# RGB_Matrix.net
KiCad netlist of a schematic drawn in Altium Designer
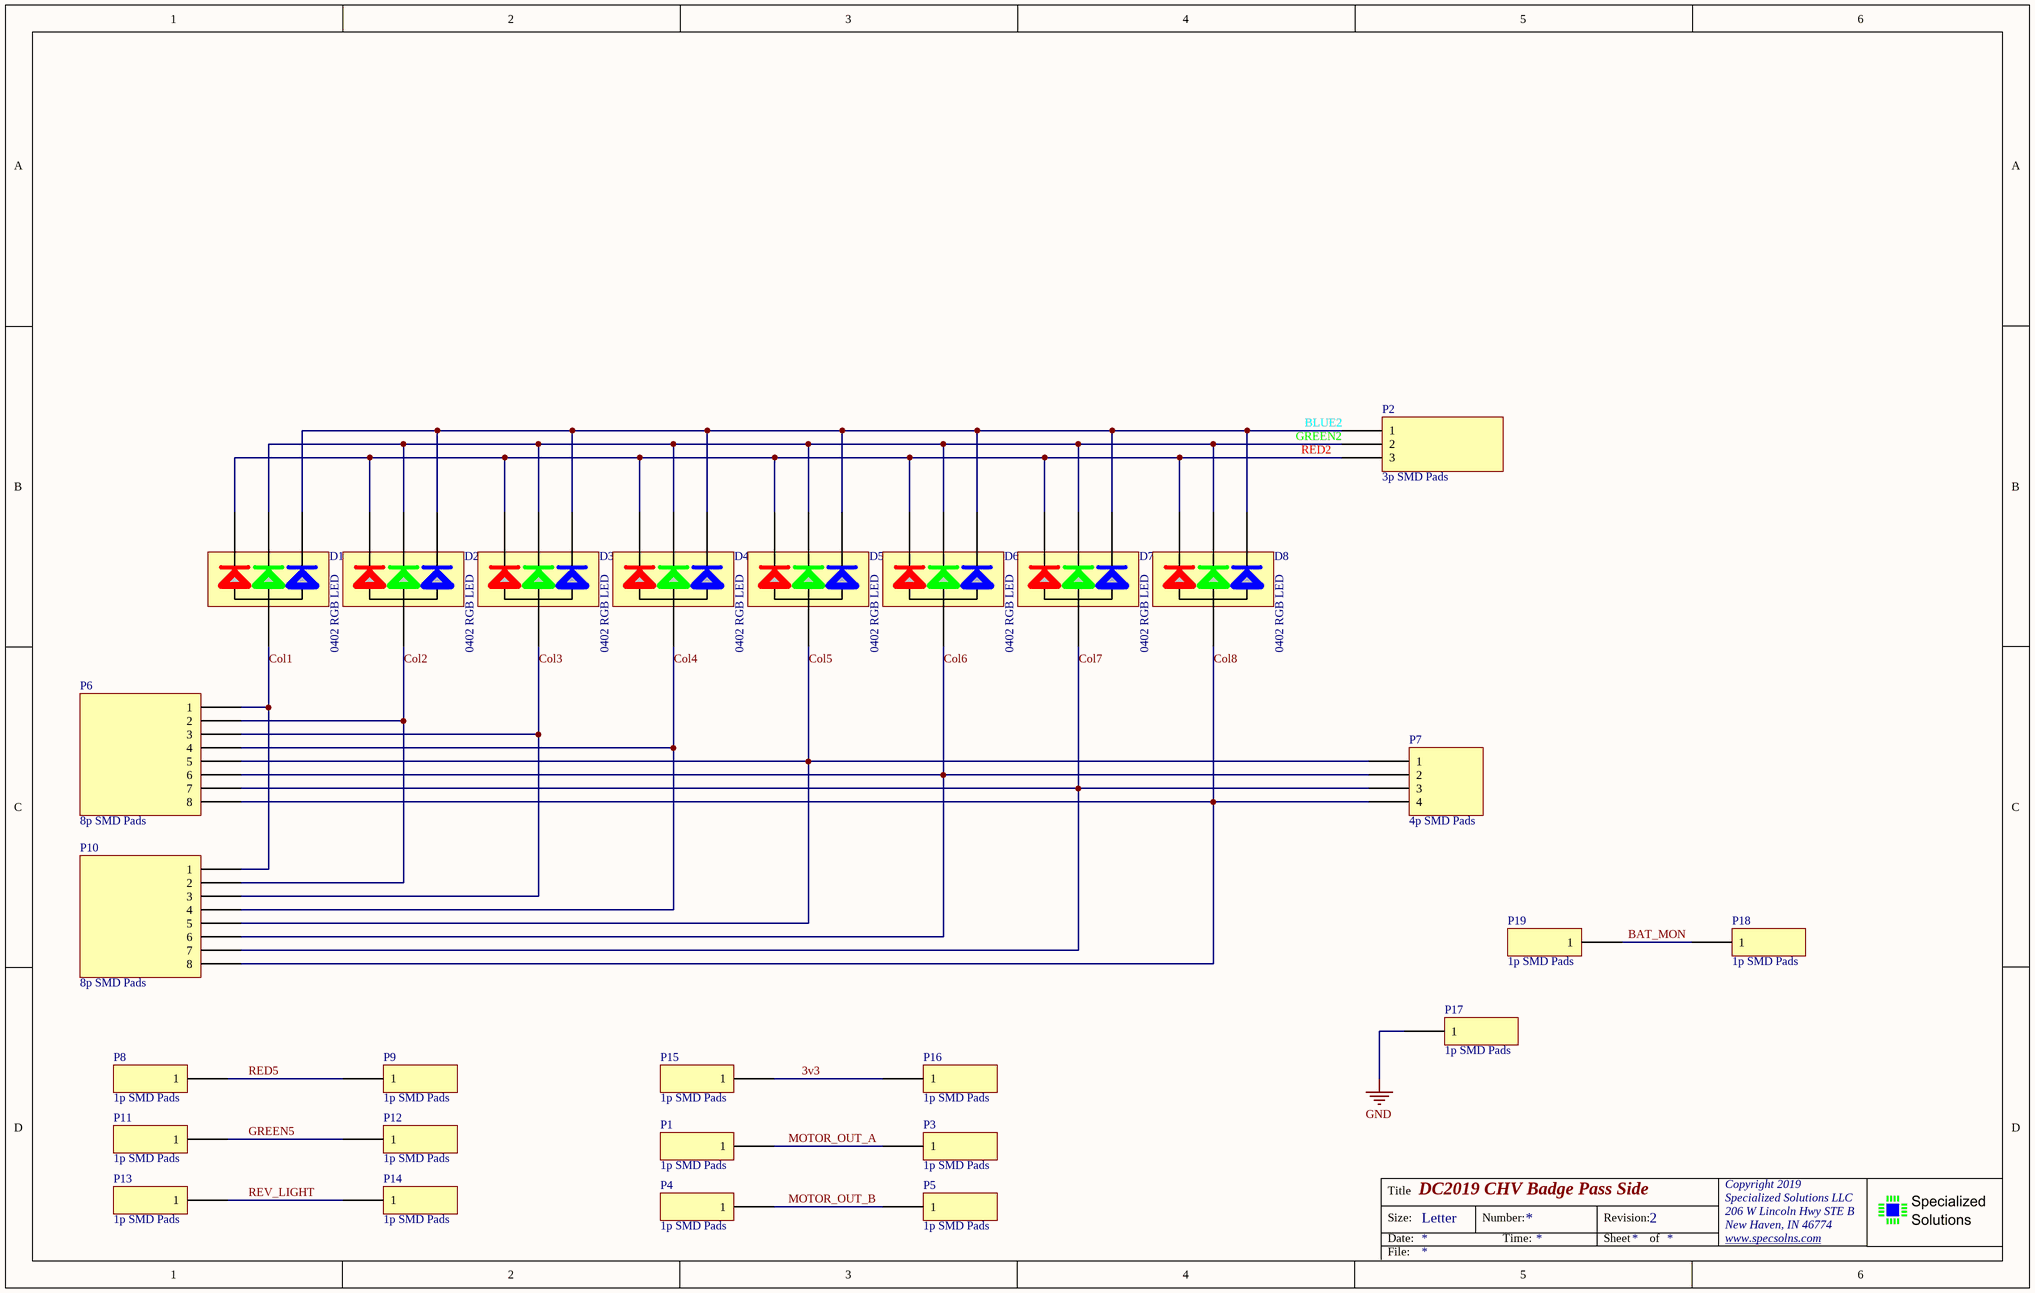
[diagram p0: RGB Matrix.SchDoc]

(export (version "E")
  (design (tool "Eeschema 10.0.6"))
  (components
    (comp (ref "D1")
      (value "0402 RGB LED")
      (footprint "0404 RGB LED")
      (libsource (lib "Parts") (part "0402 RGB LED"))
    )
    (comp (ref "D2")
      (value "0402 RGB LED")
      (footprint "0404 RGB LED")
      (libsource (lib "Parts") (part "0402 RGB LED"))
    )
    (comp (ref "D3")
      (value "0402 RGB LED")
      (footprint "0404 RGB LED")
      (libsource (lib "Parts") (part "0402 RGB LED"))
    )
    (comp (ref "D4")
      (value "0402 RGB LED")
      (footprint "0404 RGB LED")
      (libsource (lib "Parts") (part "0402 RGB LED"))
    )
    (comp (ref "D5")
      (value "0402 RGB LED")
      (footprint "0404 RGB LED")
      (libsource (lib "Parts") (part "0402 RGB LED"))
    )
    (comp (ref "D6")
      (value "0402 RGB LED")
      (footprint "0404 RGB LED")
      (libsource (lib "Parts") (part "0402 RGB LED"))
    )
    (comp (ref "D7")
      (value "0402 RGB LED")
      (footprint "0404 RGB LED")
      (libsource (lib "Parts") (part "0402 RGB LED"))
    )
    (comp (ref "D8")
      (value "0402 RGB LED")
      (footprint "0404 RGB LED")
      (libsource (lib "Parts") (part "0402 RGB LED"))
    )
    (comp (ref "P1") (value "1p SMD Pads") (footprint "1p SMD pad") (libsource (lib "") (part "1p SMD_2")))
    (comp (ref "P2")
      (value "3p SMD Pads")
      (footprint "3p SMD pad")
      (libsource (lib "parts (carol's conflicted copy 2019-04-30)") (part "3p SMD"))
    )
    (comp (ref "P3") (value "1p SMD Pads") (footprint "1p SMD pad") (libsource (lib "") (part "1p SMD_1")))
    (comp (ref "P4") (value "1p SMD Pads") (footprint "1p SMD pad") (libsource (lib "") (part "1p SMD_2")))
    (comp (ref "P5") (value "1p SMD Pads") (footprint "1p SMD pad") (libsource (lib "") (part "1p SMD_1")))
    (comp (ref "P6")
      (value "8p SMD Pads")
      (footprint "8p SMD pad")
      (libsource (lib "parts") (part "8p SMD Pads"))
    )
    (comp (ref "P7") (value "4p SMD Pads") (footprint "4p SMD pad") (libsource (lib "parts") (part "4p SMD")))
    (comp (ref "P8") (value "1p SMD Pads") (footprint "1p SMD pad") (libsource (lib "parts") (part "1p SMD")))
    (comp (ref "P9") (value "1p SMD Pads") (footprint "1p SMD pad") (libsource (lib "") (part "1p SMD_1")))
    (comp (ref "P10")
      (value "8p SMD Pads")
      (footprint "8p SMD pad")
      (libsource (lib "parts") (part "8p SMD Pads"))
    )
    (comp (ref "P11")
      (value "1p SMD Pads")
      (footprint "1p SMD pad")
      (libsource (lib "parts") (part "1p SMD"))
    )
    (comp (ref "P12") (value "1p SMD Pads") (footprint "1p SMD pad") (libsource (lib "") (part "1p SMD_1")))
    (comp (ref "P13")
      (value "1p SMD Pads")
      (footprint "1p SMD pad")
      (libsource (lib "parts") (part "1p SMD"))
    )
    (comp (ref "P14") (value "1p SMD Pads") (footprint "1p SMD pad") (libsource (lib "") (part "1p SMD_1")))
    (comp (ref "P15")
      (value "1p SMD Pads")
      (footprint "1p SMD pad")
      (libsource (lib "parts") (part "1p SMD"))
    )
    (comp (ref "P16") (value "1p SMD Pads") (footprint "1p SMD pad") (libsource (lib "") (part "1p SMD_1")))
    (comp (ref "P17") (value "1p SMD Pads") (footprint "1p SMD pad") (libsource (lib "") (part "1p SMD_1")))
    (comp (ref "P18") (value "1p SMD Pads") (footprint "1p SMD pad") (libsource (lib "") (part "1p SMD_1")))
    (comp (ref "P19")
      (value "1p SMD Pads")
      (footprint "1p SMD pad")
      (libsource (lib "parts") (part "1p SMD"))
    )
  )
  (nets
    (net (code "1") (name "/3v3") (class "Default")
      (node (ref "P15") (pin "1") (pinfunction "1_1") (pintype "passive"))
      (node (ref "P16") (pin "1") (pinfunction "1_1") (pintype "passive"))
    )
    (net (code "2") (name "/BAT_MON") (class "Default")
      (node (ref "P18") (pin "1") (pinfunction "1_1") (pintype "passive"))
      (node (ref "P19") (pin "1") (pinfunction "1_1") (pintype "passive"))
    )
    (net (code "3") (name "/BLUE2") (class "Default")
      (node (ref "D1") (pin "4") (pintype "passive"))
      (node (ref "D2") (pin "4") (pintype "passive"))
      (node (ref "D3") (pin "4") (pintype "passive"))
      (node (ref "D4") (pin "4") (pintype "passive"))
      (node (ref "D5") (pin "4") (pintype "passive"))
      (node (ref "D6") (pin "4") (pintype "passive"))
      (node (ref "D7") (pin "4") (pintype "passive"))
      (node (ref "D8") (pin "4") (pintype "passive"))
      (node (ref "P2") (pin "1") (pinfunction "1_1") (pintype "passive"))
    )
    (net (code "4") (name "/Col1") (class "Default")
      (node (ref "D1") (pin "1") (pintype "passive"))
      (node (ref "P10") (pin "1") (pinfunction "1_1") (pintype "passive"))
      (node (ref "P6") (pin "1") (pinfunction "1_1") (pintype "passive"))
    )
    (net (code "5") (name "/Col2") (class "Default")
      (node (ref "D2") (pin "1") (pintype "passive"))
      (node (ref "P10") (pin "2") (pinfunction "2_2") (pintype "passive"))
      (node (ref "P6") (pin "2") (pinfunction "2_2") (pintype "passive"))
    )
    (net (code "6") (name "/Col3") (class "Default")
      (node (ref "D3") (pin "1") (pintype "passive"))
      (node (ref "P10") (pin "3") (pinfunction "3_3") (pintype "passive"))
      (node (ref "P6") (pin "3") (pinfunction "3_3") (pintype "passive"))
    )
    (net (code "7") (name "/Col4") (class "Default")
      (node (ref "D4") (pin "1") (pintype "passive"))
      (node (ref "P10") (pin "4") (pinfunction "4_4") (pintype "passive"))
      (node (ref "P6") (pin "4") (pinfunction "4_4") (pintype "passive"))
    )
    (net (code "8") (name "/Col5") (class "Default")
      (node (ref "D5") (pin "1") (pintype "passive"))
      (node (ref "P10") (pin "5") (pinfunction "5_5") (pintype "passive"))
      (node (ref "P6") (pin "5") (pinfunction "5_5") (pintype "passive"))
      (node (ref "P7") (pin "1") (pinfunction "1_1") (pintype "passive"))
    )
    (net (code "9") (name "/Col6") (class "Default")
      (node (ref "D6") (pin "1") (pintype "passive"))
      (node (ref "P10") (pin "6") (pinfunction "6_6") (pintype "passive"))
      (node (ref "P6") (pin "6") (pinfunction "6_6") (pintype "passive"))
      (node (ref "P7") (pin "2") (pinfunction "2_2") (pintype "passive"))
    )
    (net (code "10") (name "/Col7") (class "Default")
      (node (ref "D7") (pin "1") (pintype "passive"))
      (node (ref "P10") (pin "7") (pinfunction "7_7") (pintype "passive"))
      (node (ref "P6") (pin "7") (pinfunction "7_7") (pintype "passive"))
      (node (ref "P7") (pin "3") (pinfunction "3_3") (pintype "passive"))
    )
    (net (code "11") (name "/Col8") (class "Default")
      (node (ref "D8") (pin "1") (pintype "passive"))
      (node (ref "P10") (pin "8") (pinfunction "8_8") (pintype "passive"))
      (node (ref "P6") (pin "8") (pinfunction "8_8") (pintype "passive"))
      (node (ref "P7") (pin "4") (pinfunction "4_4") (pintype "passive"))
    )
    (net (code "12") (name "/GREEN2") (class "Default")
      (node (ref "D1") (pin "3") (pintype "passive"))
      (node (ref "D2") (pin "3") (pintype "passive"))
      (node (ref "D3") (pin "3") (pintype "passive"))
      (node (ref "D4") (pin "3") (pintype "passive"))
      (node (ref "D5") (pin "3") (pintype "passive"))
      (node (ref "D6") (pin "3") (pintype "passive"))
      (node (ref "D7") (pin "3") (pintype "passive"))
      (node (ref "D8") (pin "3") (pintype "passive"))
      (node (ref "P2") (pin "2") (pinfunction "2_2") (pintype "passive"))
    )
    (net (code "13") (name "/GREEN5") (class "Default")
      (node (ref "P11") (pin "1") (pinfunction "1_1") (pintype "passive"))
      (node (ref "P12") (pin "1") (pinfunction "1_1") (pintype "passive"))
    )
    (net (code "14") (name "/MOTOR_OUT_A") (class "Default")
      (node (ref "P1") (pin "1") (pinfunction "1_1") (pintype "passive"))
      (node (ref "P3") (pin "1") (pinfunction "1_1") (pintype "passive"))
    )
    (net (code "15") (name "/MOTOR_OUT_B") (class "Default")
      (node (ref "P4") (pin "1") (pinfunction "1_1") (pintype "passive"))
      (node (ref "P5") (pin "1") (pinfunction "1_1") (pintype "passive"))
    )
    (net (code "16") (name "/RED2") (class "Default")
      (node (ref "D1") (pin "2") (pintype "passive"))
      (node (ref "D2") (pin "2") (pintype "passive"))
      (node (ref "D3") (pin "2") (pintype "passive"))
      (node (ref "D4") (pin "2") (pintype "passive"))
      (node (ref "D5") (pin "2") (pintype "passive"))
      (node (ref "D6") (pin "2") (pintype "passive"))
      (node (ref "D7") (pin "2") (pintype "passive"))
      (node (ref "D8") (pin "2") (pintype "passive"))
      (node (ref "P2") (pin "3") (pinfunction "3_3") (pintype "passive"))
    )
    (net (code "17") (name "/RED5") (class "Default")
      (node (ref "P8") (pin "1") (pinfunction "1_1") (pintype "passive"))
      (node (ref "P9") (pin "1") (pinfunction "1_1") (pintype "passive"))
    )
    (net (code "18") (name "/REV_LIGHT") (class "Default")
      (node (ref "P13") (pin "1") (pinfunction "1_1") (pintype "passive"))
      (node (ref "P14") (pin "1") (pinfunction "1_1") (pintype "passive"))
    )
    (net (code "19") (name "GND") (class "Default")
      (node (ref "P17") (pin "1") (pinfunction "1_1") (pintype "passive"))
    )
  )
)
